# Projet_Elec.net
KiCad netlist of a schematic drawn in EAGLE
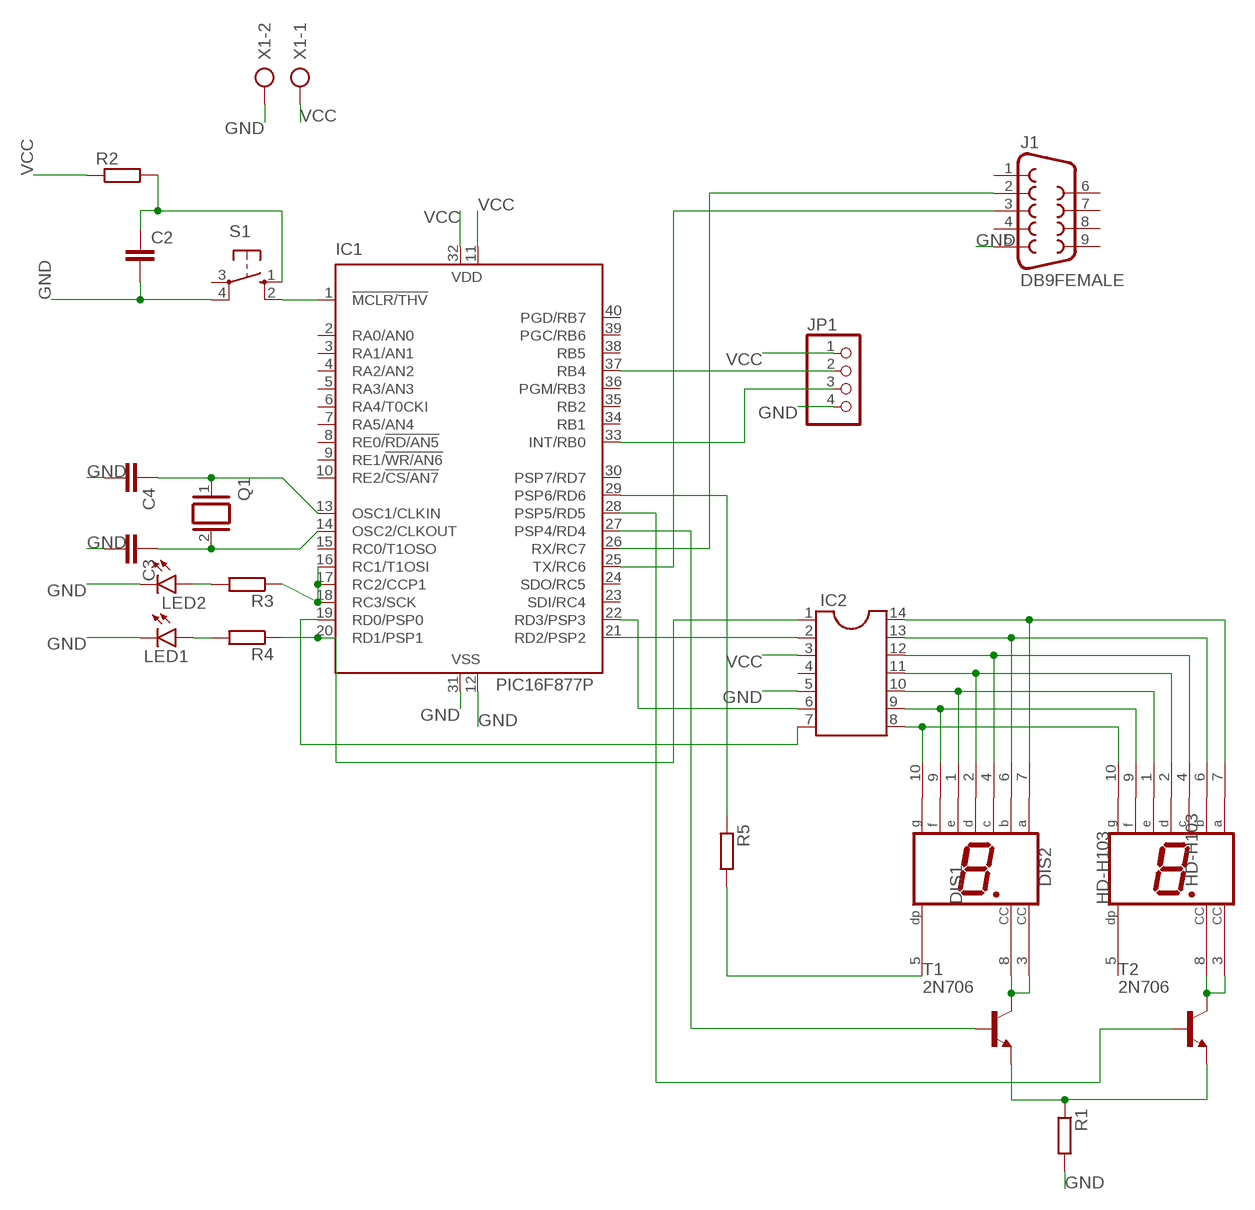
[diagram p0: schematic, sheet 1]

(export (version "E")
  (design (tool "Eeschema 10.0.6"))
  (components
    (comp (ref "C2")
      (value "C-EU025-024X044")
      (footprint "eagle-import:C025-024X044")
      (libsource (lib "eagle-import") (part "C-EU025-024X044"))
    )
    (comp (ref "C3")
      (value "C-EU025-024X044")
      (footprint "eagle-import:C025-024X044")
      (libsource (lib "eagle-import") (part "C-EU025-024X044"))
    )
    (comp (ref "C4")
      (value "C-EU025-024X044")
      (footprint "eagle-import:C025-024X044")
      (libsource (lib "eagle-import") (part "C-EU025-024X044"))
    )
    (comp (ref "DIS1")
      (value "HD-H103")
      (footprint "eagle-import:HDSP-M")
      (libsource (lib "eagle-import") (part "HD-H103"))
    )
    (comp (ref "DIS2")
      (value "HD-H103")
      (footprint "eagle-import:HDSP-M")
      (libsource (lib "eagle-import") (part "HD-H103"))
    )
    (comp (ref "IC1")
      (value "PIC16F877P")
      (footprint "eagle-import:DIL40")
      (fields (field (name "MF") "MICROCHIP") (field (name "MPN") "PIC16F877-04/P"))
      (libsource (lib "eagle-import") (part "PIC16F87P7"))
    )
    (comp (ref "IC2")
      (value "DIL14")
      (footprint "eagle-import:DIL14")
      (libsource (lib "eagle-import") (part "DIL14"))
    )
    (comp (ref "J1")
      (value "DB9FEMALE")
      (footprint "eagle-import:DB9")
      (fields (field (name "MF") "Tripp Lite") (field (name "MP") "DB9"))
      (libsource (lib "eagle-import") (part "DB9FEMALE"))
    )
    (comp (ref "JP1")
      (value "PINHD-1X4")
      (footprint "eagle-import:1X04")
      (libsource (lib "eagle-import") (part "PINHD-1X4"))
    )
    (comp (ref "LED1")
      (value "LED5MM")
      (footprint "eagle-import:LED5MM")
      (libsource (lib "eagle-import") (part "LED5MM"))
    )
    (comp (ref "LED2")
      (value "LED5MM")
      (footprint "eagle-import:LED5MM")
      (libsource (lib "eagle-import") (part "LED5MM"))
    )
    (comp (ref "Q1")
      (value "XTAL/S")
      (footprint "eagle-import:QS")
      (libsource (lib "eagle-import") (part "XTAL/S"))
    )
    (comp (ref "R1")
      (value "R-EU_0204/7")
      (footprint "eagle-import:0204_7")
      (libsource (lib "eagle-import") (part "R-EU_0204/7"))
    )
    (comp (ref "R2")
      (value "R-EU_0204/7")
      (footprint "eagle-import:0204_7")
      (libsource (lib "eagle-import") (part "R-EU_0204/7"))
    )
    (comp (ref "R3")
      (value "R-EU_0204/7")
      (footprint "eagle-import:0204_7")
      (libsource (lib "eagle-import") (part "R-EU_0204/7"))
    )
    (comp (ref "R4")
      (value "R-EU_0204/7")
      (footprint "eagle-import:0204_7")
      (libsource (lib "eagle-import") (part "R-EU_0204/7"))
    )
    (comp (ref "R5")
      (value "R-EU_0204/7")
      (footprint "eagle-import:0204_7")
      (libsource (lib "eagle-import") (part "R-EU_0204/7"))
    )
    (comp (ref "S1")
      (value "10-XX")
      (footprint "eagle-import:B3F-10XX")
      (fields (field (name "MPN") "B3F-1000"))
      (libsource (lib "eagle-import") (part "10-XX"))
    )
    (comp (ref "T1")
      (value "2N706")
      (footprint "eagle-import:TO18")
      (libsource (lib "eagle-import") (part "2N706"))
    )
    (comp (ref "T2")
      (value "2N706")
      (footprint "eagle-import:TO18")
      (libsource (lib "eagle-import") (part "2N706"))
    )
    (comp (ref "X1")
      (value "AK300/2")
      (footprint "eagle-import:AK300_2")
      (libsource (lib "eagle-import") (part "AK300/2"))
    )
  )
  (nets
    (net (code "1") (name "/GND") (class "Default")
      (node (ref "C2") (pin "2") (pinfunction "2_2") (pintype "passive"))
      (node (ref "C3") (pin "2") (pinfunction "2_2") (pintype "passive"))
      (node (ref "C4") (pin "2") (pinfunction "2_2") (pintype "passive"))
      (node (ref "IC1") (pin "12") (pinfunction "VSS_12") (pintype "power_in"))
      (node (ref "IC1") (pin "31") (pinfunction "VSS_31") (pintype "power_in"))
      (node (ref "IC2") (pin "5") (pinfunction "5_5") (pintype "passive"))
      (node (ref "J1") (pin "5") (pinfunction "5_5") (pintype "passive"))
      (node (ref "JP1") (pin "4") (pinfunction "4_4") (pintype "passive"))
      (node (ref "LED1") (pin "K") (pinfunction "C_K") (pintype "passive"))
      (node (ref "LED2") (pin "K") (pinfunction "C_K") (pintype "passive"))
      (node (ref "R1") (pin "2") (pinfunction "2_2") (pintype "passive"))
      (node (ref "S1") (pin "4") (pinfunction "P1_4") (pintype "passive"))
      (node (ref "X1") (pin "2") (pinfunction "KL_2") (pintype "passive"))
    )
    (net (code "2") (name "/VCC") (class "Default")
      (node (ref "IC1") (pin "11") (pinfunction "VDD_11") (pintype "power_in"))
      (node (ref "IC1") (pin "32") (pinfunction "VDD_32") (pintype "power_in"))
      (node (ref "IC2") (pin "3") (pinfunction "3_3") (pintype "passive"))
      (node (ref "JP1") (pin "1") (pinfunction "1_1") (pintype "passive"))
      (node (ref "R2") (pin "1") (pinfunction "1_1") (pintype "passive"))
      (node (ref "X1") (pin "1") (pinfunction "KL_1") (pintype "passive"))
    )
    (net (code "3") (name "Net-(DIS1-A)") (class "Default")
      (node (ref "DIS1") (pin "7") (pinfunction "A_7") (pintype "passive"))
      (node (ref "DIS2") (pin "7") (pinfunction "A_7") (pintype "passive"))
      (node (ref "IC2") (pin "14") (pinfunction "14_14") (pintype "passive"))
    )
    (net (code "4") (name "Net-(DIS1-B)") (class "Default")
      (node (ref "DIS1") (pin "6") (pinfunction "B_6") (pintype "passive"))
      (node (ref "DIS2") (pin "6") (pinfunction "B_6") (pintype "passive"))
      (node (ref "IC2") (pin "13") (pinfunction "13_13") (pintype "passive"))
    )
    (net (code "5") (name "Net-(DIS1-C)") (class "Default")
      (node (ref "DIS1") (pin "4") (pinfunction "C_4") (pintype "passive"))
      (node (ref "DIS2") (pin "4") (pinfunction "C_4") (pintype "passive"))
      (node (ref "IC2") (pin "12") (pinfunction "12_12") (pintype "passive"))
    )
    (net (code "6") (name "Net-(DIS1-D)") (class "Default")
      (node (ref "DIS1") (pin "2") (pinfunction "D_2") (pintype "passive"))
      (node (ref "DIS2") (pin "2") (pinfunction "D_2") (pintype "passive"))
      (node (ref "IC2") (pin "11") (pinfunction "11_11") (pintype "passive"))
    )
    (net (code "7") (name "Net-(DIS1-DP)") (class "Default")
      (node (ref "DIS1") (pin "5") (pinfunction "DP_5") (pintype "passive"))
      (node (ref "R5") (pin "2") (pinfunction "2_2") (pintype "passive"))
    )
    (net (code "8") (name "Net-(DIS1-E)") (class "Default")
      (node (ref "DIS1") (pin "1") (pinfunction "E_1") (pintype "passive"))
      (node (ref "DIS2") (pin "1") (pinfunction "E_1") (pintype "passive"))
      (node (ref "IC2") (pin "10") (pinfunction "10_10") (pintype "passive"))
    )
    (net (code "9") (name "Net-(DIS1-F)") (class "Default")
      (node (ref "DIS1") (pin "9") (pinfunction "F_9") (pintype "passive"))
      (node (ref "DIS2") (pin "9") (pinfunction "F_9") (pintype "passive"))
      (node (ref "IC2") (pin "9") (pinfunction "9_9") (pintype "passive"))
    )
    (net (code "10") (name "Net-(DIS1-G)") (class "Default")
      (node (ref "DIS1") (pin "10") (pinfunction "G_10") (pintype "passive"))
      (node (ref "DIS2") (pin "10") (pinfunction "G_10") (pintype "passive"))
      (node (ref "IC2") (pin "8") (pinfunction "8_8") (pintype "passive"))
    )
    (net (code "11") (name "Net-(IC1-INT{slash}RB0)") (class "Default")
      (node (ref "IC1") (pin "33") (pinfunction "INT/RB0_33") (pintype "bidirectional"))
      (node (ref "JP1") (pin "3") (pinfunction "3_3") (pintype "passive"))
    )
    (net (code "12") (name "Net-(IC1-OSC1{slash}CLKIN)") (class "Default")
      (node (ref "C4") (pin "1") (pinfunction "1_1") (pintype "passive"))
      (node (ref "IC1") (pin "13") (pinfunction "OSC1/CLKIN_13") (pintype "input"))
      (node (ref "Q1") (pin "1") (pinfunction "1_1") (pintype "passive"))
    )
    (net (code "13") (name "Net-(IC1-OSC2{slash}CLKOUT)") (class "Default")
      (node (ref "C3") (pin "1") (pinfunction "1_1") (pintype "passive"))
      (node (ref "IC1") (pin "14") (pinfunction "OSC2/CLKOUT_14") (pintype "output"))
      (node (ref "Q1") (pin "2") (pinfunction "2_2") (pintype "passive"))
    )
    (net (code "14") (name "Net-(IC1-PSP4{slash}RD4)") (class "Default")
      (node (ref "IC1") (pin "27") (pinfunction "PSP4/RD4_27") (pintype "bidirectional"))
      (node (ref "T1") (pin "2") (pinfunction "B_2") (pintype "passive"))
    )
    (net (code "15") (name "Net-(IC1-PSP5{slash}RD5)") (class "Default")
      (node (ref "IC1") (pin "28") (pinfunction "PSP5/RD5_28") (pintype "bidirectional"))
      (node (ref "T2") (pin "2") (pinfunction "B_2") (pintype "passive"))
    )
    (net (code "16") (name "Net-(IC1-PSP6{slash}RD6)") (class "Default")
      (node (ref "IC1") (pin "29") (pinfunction "PSP6/RD6_29") (pintype "bidirectional"))
      (node (ref "R5") (pin "1") (pinfunction "1_1") (pintype "passive"))
    )
    (net (code "17") (name "Net-(IC1-RB4)") (class "Default")
      (node (ref "IC1") (pin "37") (pinfunction "RB4_37") (pintype "bidirectional"))
      (node (ref "JP1") (pin "2") (pinfunction "2_2") (pintype "passive"))
    )
    (net (code "18") (name "Net-(IC1-RC1{slash}T1OSI)") (class "Default")
      (node (ref "IC1") (pin "16") (pinfunction "RC1/T1OSI_16") (pintype "bidirectional"))
      (node (ref "IC1") (pin "17") (pinfunction "RC2/CCP1_17") (pintype "bidirectional"))
      (node (ref "IC1") (pin "18") (pinfunction "RC3/SCK_18") (pintype "bidirectional"))
      (node (ref "R3") (pin "1") (pinfunction "1_1") (pintype "passive"))
    )
    (net (code "19") (name "Net-(IC1-RD0{slash}PSP0)") (class "Default")
      (node (ref "IC1") (pin "19") (pinfunction "RD0/PSP0_19") (pintype "bidirectional"))
      (node (ref "IC2") (pin "7") (pinfunction "7_7") (pintype "passive"))
    )
    (net (code "20") (name "Net-(IC1-RD1{slash}PSP1)") (class "Default")
      (node (ref "IC1") (pin "20") (pinfunction "RD1/PSP1_20") (pintype "bidirectional"))
      (node (ref "IC2") (pin "1") (pinfunction "1_1") (pintype "passive"))
      (node (ref "R4") (pin "1") (pinfunction "1_1") (pintype "passive"))
    )
    (net (code "21") (name "Net-(IC1-RD2{slash}PSP2)") (class "Default")
      (node (ref "IC1") (pin "21") (pinfunction "RD2/PSP2_21") (pintype "bidirectional"))
      (node (ref "IC2") (pin "2") (pinfunction "2_2") (pintype "passive"))
    )
    (net (code "22") (name "Net-(IC1-RD3{slash}PSP3)") (class "Default")
      (node (ref "IC1") (pin "22") (pinfunction "RD3/PSP3_22") (pintype "bidirectional"))
      (node (ref "IC2") (pin "6") (pinfunction "6_6") (pintype "passive"))
    )
    (net (code "23") (name "Net-(IC1-RX{slash}RC7)") (class "Default")
      (node (ref "IC1") (pin "26") (pinfunction "RX/RC7_26") (pintype "bidirectional"))
      (node (ref "J1") (pin "2") (pinfunction "2_2") (pintype "passive"))
    )
    (net (code "24") (name "Net-(IC1-TX{slash}RC6)") (class "Default")
      (node (ref "IC1") (pin "25") (pinfunction "TX/RC6_25") (pintype "bidirectional"))
      (node (ref "J1") (pin "3") (pinfunction "3_3") (pintype "passive"))
    )
    (net (code "25") (name "Net-(IC1-~{MCLR{slash}THV})") (class "Default")
      (node (ref "IC1") (pin "1") (pinfunction "~{MCLR/THV}_1") (pintype "input"))
      (node (ref "S1") (pin "2") (pinfunction "S1_2") (pintype "passive"))
    )
    (net (code "26") (name "Net-(LED1-PadA)") (class "Default")
      (node (ref "LED1") (pin "A") (pinfunction "A_A") (pintype "passive"))
      (node (ref "R4") (pin "2") (pinfunction "2_2") (pintype "passive"))
    )
    (net (code "27") (name "Net-(LED2-PadA)") (class "Default")
      (node (ref "LED2") (pin "A") (pinfunction "A_A") (pintype "passive"))
      (node (ref "R3") (pin "2") (pinfunction "2_2") (pintype "passive"))
    )
    (net (code "28") (name "Net-(S1-S)") (class "Default")
      (node (ref "C2") (pin "1") (pinfunction "1_1") (pintype "passive"))
      (node (ref "R2") (pin "2") (pinfunction "2_2") (pintype "passive"))
      (node (ref "S1") (pin "1") (pinfunction "S_1") (pintype "passive"))
    )
    (net (code "29") (name "Net-(T1-C)") (class "Default")
      (node (ref "DIS1") (pin "3") (pinfunction "CC_3") (pintype "passive"))
      (node (ref "DIS1") (pin "8") (pinfunction "CC_8") (pintype "passive"))
      (node (ref "T1") (pin "3") (pinfunction "C_3") (pintype "passive"))
    )
    (net (code "30") (name "Net-(T1-E)") (class "Default")
      (node (ref "R1") (pin "1") (pinfunction "1_1") (pintype "passive"))
      (node (ref "T1") (pin "1") (pinfunction "E_1") (pintype "passive"))
      (node (ref "T2") (pin "1") (pinfunction "E_1") (pintype "passive"))
    )
    (net (code "31") (name "Net-(T2-C)") (class "Default")
      (node (ref "DIS2") (pin "3") (pinfunction "CC_3") (pintype "passive"))
      (node (ref "DIS2") (pin "8") (pinfunction "CC_8") (pintype "passive"))
      (node (ref "T2") (pin "3") (pinfunction "C_3") (pintype "passive"))
    )
    (net (code "32") (name "unconnected-(DIS2-DP-Pad5)") (class "Default")
      (node (ref "DIS2") (pin "5") (pinfunction "DP_5") (pintype "passive"))
    )
    (net (code "33") (name "unconnected-(IC1-PGC{slash}RB6-Pad39)") (class "Default")
      (node (ref "IC1") (pin "39") (pinfunction "PGC/RB6_39") (pintype "bidirectional"))
    )
    (net (code "34") (name "unconnected-(IC1-PGD{slash}RB7-Pad40)") (class "Default")
      (node (ref "IC1") (pin "40") (pinfunction "PGD/RB7_40") (pintype "bidirectional"))
    )
    (net (code "35") (name "unconnected-(IC1-PGM{slash}RB3-Pad36)") (class "Default")
      (node (ref "IC1") (pin "36") (pinfunction "PGM/RB3_36") (pintype "bidirectional"))
    )
    (net (code "36") (name "unconnected-(IC1-PSP7{slash}RD7-Pad30)") (class "Default")
      (node (ref "IC1") (pin "30") (pinfunction "PSP7/RD7_30") (pintype "bidirectional"))
    )
    (net (code "37") (name "unconnected-(IC1-RA0{slash}AN0-Pad2)") (class "Default")
      (node (ref "IC1") (pin "2") (pinfunction "RA0/AN0_2") (pintype "bidirectional"))
    )
    (net (code "38") (name "unconnected-(IC1-RA1{slash}AN1-Pad3)") (class "Default")
      (node (ref "IC1") (pin "3") (pinfunction "RA1/AN1_3") (pintype "bidirectional"))
    )
    (net (code "39") (name "unconnected-(IC1-RA2{slash}AN2-Pad4)") (class "Default")
      (node (ref "IC1") (pin "4") (pinfunction "RA2/AN2_4") (pintype "bidirectional"))
    )
    (net (code "40") (name "unconnected-(IC1-RA3{slash}AN3-Pad5)") (class "Default")
      (node (ref "IC1") (pin "5") (pinfunction "RA3/AN3_5") (pintype "bidirectional"))
    )
    (net (code "41") (name "unconnected-(IC1-RA4{slash}T0CKI-Pad6)") (class "Default")
      (node (ref "IC1") (pin "6") (pinfunction "RA4/T0CKI_6") (pintype "bidirectional"))
    )
    (net (code "42") (name "unconnected-(IC1-RA5{slash}AN4-Pad7)") (class "Default")
      (node (ref "IC1") (pin "7") (pinfunction "RA5/AN4_7") (pintype "bidirectional"))
    )
    (net (code "43") (name "unconnected-(IC1-RB1-Pad34)") (class "Default")
      (node (ref "IC1") (pin "34") (pinfunction "RB1_34") (pintype "bidirectional"))
    )
    (net (code "44") (name "unconnected-(IC1-RB2-Pad35)") (class "Default")
      (node (ref "IC1") (pin "35") (pinfunction "RB2_35") (pintype "bidirectional"))
    )
    (net (code "45") (name "unconnected-(IC1-RB5-Pad38)") (class "Default")
      (node (ref "IC1") (pin "38") (pinfunction "RB5_38") (pintype "bidirectional"))
    )
    (net (code "46") (name "unconnected-(IC1-RC0{slash}T1OSO-Pad15)") (class "Default")
      (node (ref "IC1") (pin "15") (pinfunction "RC0/T1OSO_15") (pintype "bidirectional"))
    )
    (net (code "47") (name "unconnected-(IC1-RE0{slash}~{RD{slash}AN5}-Pad8)") (class "Default")
      (node (ref "IC1") (pin "8") (pinfunction "RE0/~{RD/AN5}_8") (pintype "bidirectional"))
    )
    (net (code "48") (name "unconnected-(IC1-RE1{slash}~{WR{slash}AN6}-Pad9)") (class "Default")
      (node (ref "IC1") (pin "9") (pinfunction "RE1/~{WR/AN6}_9") (pintype "bidirectional"))
    )
    (net (code "49") (name "unconnected-(IC1-RE2{slash}~{CS{slash}AN7}-Pad10)") (class "Default")
      (node (ref "IC1") (pin "10") (pinfunction "RE2/~{CS/AN7}_10") (pintype "bidirectional"))
    )
    (net (code "50") (name "unconnected-(IC1-SDI{slash}RC4-Pad23)") (class "Default")
      (node (ref "IC1") (pin "23") (pinfunction "SDI/RC4_23") (pintype "bidirectional"))
    )
    (net (code "51") (name "unconnected-(IC1-SDO{slash}RC5-Pad24)") (class "Default")
      (node (ref "IC1") (pin "24") (pinfunction "SDO/RC5_24") (pintype "bidirectional"))
    )
    (net (code "52") (name "unconnected-(IC2-Pad4)") (class "Default")
      (node (ref "IC2") (pin "4") (pinfunction "4_4") (pintype "passive"))
    )
    (net (code "53") (name "unconnected-(J1-Pad1)") (class "Default")
      (node (ref "J1") (pin "1") (pinfunction "1_1") (pintype "passive"))
    )
    (net (code "54") (name "unconnected-(J1-Pad4)") (class "Default")
      (node (ref "J1") (pin "4") (pinfunction "4_4") (pintype "passive"))
    )
    (net (code "55") (name "unconnected-(J1-Pad6)") (class "Default")
      (node (ref "J1") (pin "6") (pinfunction "6_6") (pintype "passive"))
    )
    (net (code "56") (name "unconnected-(J1-Pad7)") (class "Default")
      (node (ref "J1") (pin "7") (pinfunction "7_7") (pintype "passive"))
    )
    (net (code "57") (name "unconnected-(J1-Pad8)") (class "Default")
      (node (ref "J1") (pin "8") (pinfunction "8_8") (pintype "passive"))
    )
    (net (code "58") (name "unconnected-(J1-Pad9)") (class "Default")
      (node (ref "J1") (pin "9") (pinfunction "9_9") (pintype "passive"))
    )
    (net (code "59") (name "unconnected-(S1-P-Pad3)") (class "Default")
      (node (ref "S1") (pin "3") (pinfunction "P_3") (pintype "passive"))
    )
  )
)
